# 1_P1.net
KiCad netlist of a schematic drawn in Altium Designer
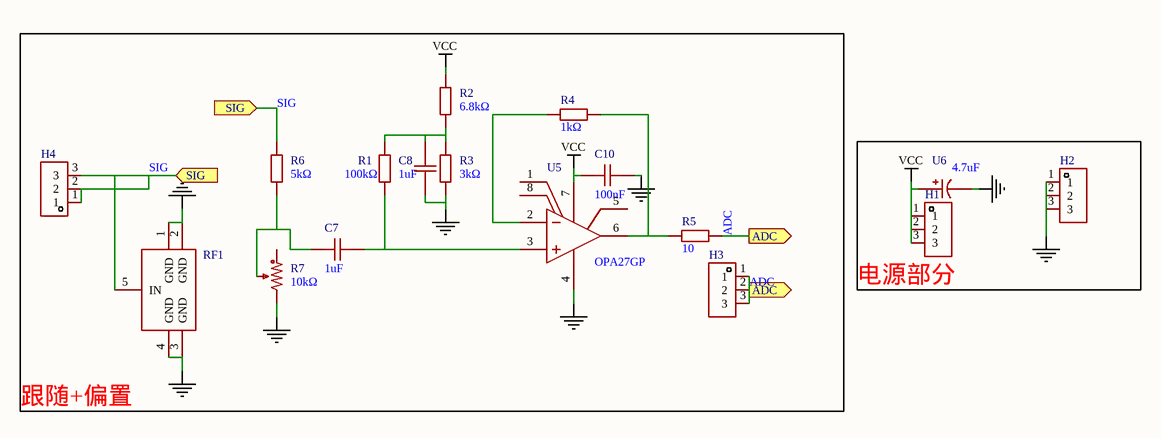
[diagram p0: 1_P1.schdoc]

(export (version "E")
  (design (tool "Eeschema 10.0.6"))
  (components
    (comp (ref "C7")
      (value "1uF")
      (footprint "CAP-TH_L5.5-W3.8-P3.50-D0.6")
      (fields
        (field (name "MANUFACTURER") "Dersonic(德尔创)")
        (field (name "MANUFACTURER PART") "CD1E106MC9BER2F100")
        (field (name "TOLERANCE") "±20%")
      )
      (libsource (lib "altium-import") (part "root_0_CD1E106MC9BER2F100_"))
    )
    (comp (ref "C8")
      (value "1uF")
      (footprint "CAP-TH_L5.5-W3.8-P3.50-D0.6")
      (fields
        (field (name "MANUFACTURER") "Dersonic(德尔创)")
        (field (name "MANUFACTURER PART") "CD1E106MC9BER2F100")
        (field (name "TOLERANCE") "±20%")
      )
      (libsource (lib "altium-import") (part "root_1_CD1E106MC9BER2F100_"))
    )
    (comp (ref "C10")
      (value "100nF")
      (footprint "CAP-TH_L5.0-W2.5-P5.00-D1.0")
      (fields
        (field (name "MANUFACTURER") "Dersonic(德尔创)")
        (field (name "MANUFACTURER PART") "CC1H104MC1FD3F6C10MF")
        (field (name "TOLERANCE") "±20%")
      )
      (libsource (lib "altium-import") (part "root_0_CC1H104MC1FD3F6C10MF_"))
    )
    (comp (ref "H1")
      (value "PZ254V-11-03P")
      (footprint "HDR-TH_3P-P2.54-V-M")
      (fields (field (name "MANUFACTURER") "XFCN(兴飞)"))
      (libsource (lib "altium-import") (part "root_0_PZ254V-11-03P_"))
    )
    (comp (ref "H2")
      (value "PZ254V-11-03P")
      (footprint "HDR-TH_3P-P2.54-V-M")
      (fields (field (name "MANUFACTURER") "XFCN(兴飞)"))
      (libsource (lib "altium-import") (part "root_0_PZ254V-11-03P_"))
    )
    (comp (ref "H3")
      (value "PZ254V-11-03P")
      (footprint "HDR-TH_3P-P2.54-V-M")
      (fields (field (name "MANUFACTURER") "XFCN(兴飞)"))
      (libsource (lib "altium-import") (part "root_0_mirrored_PZ254V-11-03P_"))
    )
    (comp (ref "H4")
      (value "PZ254V-11-03P")
      (footprint "HDR-TH_3P-P2.54-V-M")
      (fields (field (name "MANUFACTURER") "XFCN(兴飞)"))
      (libsource (lib "altium-import") (part "root_2_PZ254V-11-03P_"))
    )
    (comp (ref "R1")
      (value "100kΩ")
      (footprint "RES-TH_BD2.7-L6.2-P10.20-D0.4")
      (fields
        (field (name "MANUFACTURER") "VO(翔胜)")
        (field (name "MANUFACTURER PART") "MF1/4W-100K±1%-OT26")
        (field (name "TOLERANCE") "±1%")
      )
      (libsource (lib "altium-import") (part "root_1_MF1/4W-100K±1%-OT26_"))
    )
    (comp (ref "R2")
      (value "6.8kΩ")
      (footprint "RES-TH_BD2.7-L6.2-P10.20-D0.4")
      (fields
        (field (name "MANUFACTURER") "VO(翔胜)")
        (field (name "MANUFACTURER PART") "MF1/4W-100K±1%-OT26")
        (field (name "TOLERANCE") "±1%")
      )
      (libsource (lib "altium-import") (part "root_1_MF1/4W-100K±1%-OT26_"))
    )
    (comp (ref "R3")
      (value "3kΩ")
      (footprint "RES-TH_BD2.7-L6.2-P10.20-D0.4")
      (fields
        (field (name "MANUFACTURER") "VO(翔胜)")
        (field (name "MANUFACTURER PART") "MF1/4W-100K±1%-OT26")
        (field (name "TOLERANCE") "±1%")
      )
      (libsource (lib "altium-import") (part "root_1_MF1/4W-100K±1%-OT26_"))
    )
    (comp (ref "R4")
      (value "1kΩ")
      (footprint "RES-TH_BD2.3-L6.5-P10.50-D0.5")
      (fields
        (field (name "MANUFACTURER") "CCO(千志电子)")
        (field (name "MANUFACTURER PART") "MF1/4W-20KΩ±1% T")
        (field (name "TOLERANCE") "±1%")
      )
      (libsource (lib "altium-import") (part "root_2_MF1/4W-20KΩ±1% T_"))
    )
    (comp (ref "R5")
      (value "10")
      (footprint "RES-TH_BD2.3-L6.5-P10.50-D0.5")
      (fields
        (field (name "MANUFACTURER") "CCO(千志电子)")
        (field (name "MANUFACTURER PART") "MF1/4W-20KΩ±1% T")
        (field (name "TOLERANCE") "±1%")
      )
      (libsource (lib "altium-import") (part "root_2_MF1/4W-20KΩ±1% T_"))
    )
    (comp (ref "R6")
      (value "5kΩ")
      (footprint "RES-TH_BD2.7-L6.2-P10.20-D0.4")
      (fields
        (field (name "MANUFACTURER") "VO(翔胜)")
        (field (name "MANUFACTURER PART") "MF1/4W-100K±1%-OT26")
        (field (name "TOLERANCE") "±1%")
      )
      (libsource (lib "altium-import") (part "root_1_MF1/4W-100K±1%-OT26_"))
    )
    (comp (ref "R7")
      (value "10kΩ")
      (footprint "RES-ADJ-TH_3P-L10.0-W10.0-P2.50-L")
      (fields
        (field (name "MANUFACTURER") "BOCHEN(博晨)")
        (field (name "MANUFACTURER PART") "3296W-1-103")
        (field (name "TOLERANCE") "±10%")
      )
      (libsource (lib "altium-import") (part "root_1_3296W-1-103_"))
    )
    (comp (ref "RF1")
      (value "KH-SMA-K513-G")
      (footprint "ANT-TH_KH-SMA-K513-G")
      (fields (field (name "MANUFACTURER") "kinghelm(金航标)"))
      (libsource (lib "altium-import") (part "root_3_KH-SMA-K513-G_"))
    )
    (comp (ref "U5")
      (value "OPA27GP")
      (footprint "PDIP-8_L9.6-W6.4-P2.54-LS7.6-BL")
      (fields (field (name "MANUFACTURER") "TI(德州仪器)"))
      (libsource (lib "altium-import") (part "root_0_OPA27GP_"))
    )
    (comp (ref "U6")
      (value "4.7uF")
      (footprint "CAP-TH_BD8.0-P3.50-D0.6-FD_1")
      (fields
        (field (name "MANUFACTURER") "KNSCHA(科尼盛)")
        (field (name "MANUFACTURER PART") "87EC0068")
        (field (name "TOLERANCE") "±20%")
      )
      (libsource (lib "altium-import") (part "root_0_87EC0068_"))
    )
  )
  (nets
    (net (code "1") (name "/ADC") (class "Default")
      (node (ref "H3") (pin "1") (pinfunction "1_1") (pintype "passive"))
      (node (ref "H3") (pin "2") (pinfunction "2_2") (pintype "passive"))
      (node (ref "H3") (pin "3") (pinfunction "3_3") (pintype "passive"))
      (node (ref "R5") (pin "1") (pinfunction "1_1") (pintype "passive"))
    )
    (net (code "2") (name "/SIG") (class "Default")
      (node (ref "H4") (pin "1") (pinfunction "1_1") (pintype "passive"))
      (node (ref "H4") (pin "2") (pinfunction "2_2") (pintype "passive"))
      (node (ref "H4") (pin "3") (pinfunction "3_3") (pintype "passive"))
      (node (ref "R6") (pin "2") (pinfunction "2_2") (pintype "passive"))
      (node (ref "RF1") (pin "5") (pinfunction "IN_5") (pintype "passive"))
    )
    (net (code "3") (name "GND") (class "Default")
      (node (ref "C10") (pin "2") (pinfunction "2_2") (pintype "passive"))
      (node (ref "C8") (pin "1") (pinfunction "1_1") (pintype "passive"))
      (node (ref "H2") (pin "1") (pinfunction "1_1") (pintype "passive"))
      (node (ref "H2") (pin "2") (pinfunction "2_2") (pintype "passive"))
      (node (ref "H2") (pin "3") (pinfunction "3_3") (pintype "passive"))
      (node (ref "R3") (pin "1") (pinfunction "1_1") (pintype "passive"))
      (node (ref "R7") (pin "3") (pinfunction "3_3") (pintype "passive"))
      (node (ref "RF1") (pin "1") (pinfunction "GND_1") (pintype "passive"))
      (node (ref "RF1") (pin "2") (pinfunction "GND_2") (pintype "passive"))
      (node (ref "RF1") (pin "3") (pinfunction "GND_3") (pintype "passive"))
      (node (ref "RF1") (pin "4") (pinfunction "GND_4") (pintype "passive"))
      (node (ref "U5") (pin "4") (pinfunction "-VCC_4") (pintype "passive"))
      (node (ref "U6") (pin "2") (pinfunction "2_2") (pintype "passive"))
    )
    (net (code "4") (name "Net-(C7-Pad1)") (class "Default")
      (node (ref "C7") (pin "1") (pinfunction "1_1") (pintype "passive"))
      (node (ref "R6") (pin "1") (pinfunction "1_1") (pintype "passive"))
      (node (ref "R7") (pin "2") (pinfunction "2_2") (pintype "passive"))
    )
    (net (code "5") (name "Net-(C8-Pad2)") (class "Default")
      (node (ref "C8") (pin "2") (pinfunction "2_2") (pintype "passive"))
      (node (ref "R1") (pin "2") (pinfunction "2_2") (pintype "passive"))
      (node (ref "R2") (pin "1") (pinfunction "1_1") (pintype "passive"))
      (node (ref "R3") (pin "2") (pinfunction "2_2") (pintype "passive"))
    )
    (net (code "6") (name "Net-(U5-IN+)") (class "Default")
      (node (ref "C7") (pin "2") (pinfunction "2_2") (pintype "passive"))
      (node (ref "R1") (pin "1") (pinfunction "1_1") (pintype "passive"))
      (node (ref "U5") (pin "3") (pinfunction "IN+_3") (pintype "passive"))
    )
    (net (code "7") (name "Net-(U5-IN-)") (class "Default")
      (node (ref "R4") (pin "2") (pinfunction "2_2") (pintype "passive"))
      (node (ref "U5") (pin "2") (pinfunction "IN-_2") (pintype "passive"))
    )
    (net (code "8") (name "Net-(U5-OUT)") (class "Default")
      (node (ref "R4") (pin "1") (pinfunction "1_1") (pintype "passive"))
      (node (ref "R5") (pin "2") (pinfunction "2_2") (pintype "passive"))
      (node (ref "U5") (pin "6") (pinfunction "OUT_6") (pintype "passive"))
    )
    (net (code "9") (name "VCC") (class "Default")
      (node (ref "C10") (pin "1") (pinfunction "1_1") (pintype "passive"))
      (node (ref "H1") (pin "1") (pinfunction "1_1") (pintype "passive"))
      (node (ref "H1") (pin "2") (pinfunction "2_2") (pintype "passive"))
      (node (ref "H1") (pin "3") (pinfunction "3_3") (pintype "passive"))
      (node (ref "R2") (pin "2") (pinfunction "2_2") (pintype "passive"))
      (node (ref "U5") (pin "7") (pinfunction "+VCC_7") (pintype "passive"))
      (node (ref "U6") (pin "1") (pinfunction "1_1") (pintype "passive"))
    )
    (net (code "10") (name "unconnected-(R7-Pad1)") (class "Default")
      (node (ref "R7") (pin "1") (pinfunction "1_1") (pintype "passive"))
    )
    (net (code "11") (name "unconnected-(U5-NC-Pad5)") (class "Default")
      (node (ref "U5") (pin "5") (pinfunction "NC_5") (pintype "passive"))
    )
    (net (code "12") (name "unconnected-(U5-Offset_Trim-Pad1)") (class "Default")
      (node (ref "U5") (pin "1") (pinfunction "Offset_Trim_1") (pintype "passive"))
    )
    (net (code "13") (name "unconnected-(U5-Offset_Trim-Pad8)") (class "Default")
      (node (ref "U5") (pin "8") (pinfunction "Offset_Trim_8") (pintype "passive"))
    )
  )
)
